# dcdc.net
KiCad netlist of a schematic drawn in EAGLE
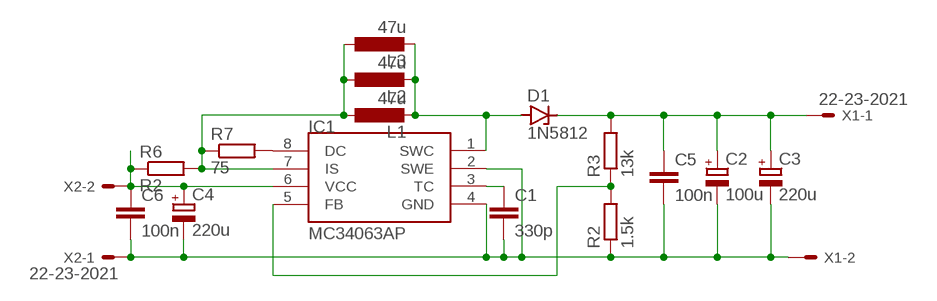
[diagram p0: schematic, sheet 1]

(export (version "E")
  (design (tool "Eeschema 10.0.6"))
  (components
    (comp (ref "C1")
      (value "330p")
      (footprint "eagle-import:C0805")
      (libsource (lib "eagle-import") (part "C-EUC0805"))
    )
    (comp (ref "C2")
      (value "100u")
      (footprint "eagle-import:E5-8,5")
      (libsource (lib "eagle-import") (part "CPOL-EUE5-8.5"))
    )
    (comp (ref "C3")
      (value "220u")
      (footprint "eagle-import:E5-8,5")
      (libsource (lib "eagle-import") (part "CPOL-EUE5-8.5"))
    )
    (comp (ref "C4")
      (value "220u")
      (footprint "eagle-import:E5-8,5")
      (libsource (lib "eagle-import") (part "CPOL-EUE5-8.5"))
    )
    (comp (ref "C5")
      (value "100n")
      (footprint "eagle-import:C0805")
      (libsource (lib "eagle-import") (part "C-EUC0805"))
    )
    (comp (ref "C6")
      (value "100n")
      (footprint "eagle-import:C0805")
      (libsource (lib "eagle-import") (part "C-EUC0805"))
    )
    (comp (ref "D1")
      (value "1N5812")
      (footprint "eagle-import:C1702-15")
      (libsource (lib "eagle-import") (part "1N5333"))
    )
    (comp (ref "IC1")
      (value "MC34063AP")
      (footprint "eagle-import:DIL08")
      (libsource (lib "eagle-import") (part "MC34063AP"))
    )
    (comp (ref "L1")
      (value "47u")
      (footprint "eagle-import:TJ3-U2")
      (libsource (lib "eagle-import") (part "L-EUTJ3-U2"))
    )
    (comp (ref "L2")
      (value "47u")
      (footprint "eagle-import:TJ4-U2")
      (libsource (lib "eagle-import") (part "L-EUTJ4-U2"))
    )
    (comp (ref "L3")
      (value "47u")
      (footprint "eagle-import:6000-XXXX-RC")
      (libsource (lib "eagle-import") (part "L-EU6000-XXX-RC"))
    )
    (comp (ref "R2")
      (value "1.5k")
      (footprint "eagle-import:R0805")
      (libsource (lib "eagle-import") (part "R-EU_R0805"))
    )
    (comp (ref "R3")
      (value "13k")
      (footprint "eagle-import:0204_7")
      (libsource (lib "eagle-import") (part "R-EU_0204/7"))
    )
    (comp (ref "R6")
      (value "R2")
      (footprint "eagle-import:R0805")
      (libsource (lib "eagle-import") (part "R-EU_R0805"))
    )
    (comp (ref "R7")
      (value "75")
      (footprint "eagle-import:R0805")
      (libsource (lib "eagle-import") (part "R-EU_R0805"))
    )
    (comp (ref "X1")
      (value "22-23-2021")
      (footprint "eagle-import:22-23-2021")
      (fields (field (name "MF") "MOLEX"))
      (libsource (lib "eagle-import") (part "22-23-2021"))
    )
    (comp (ref "X2")
      (value "22-23-2021")
      (footprint "eagle-import:22-23-2021")
      (fields (field (name "MF") "MOLEX"))
      (libsource (lib "eagle-import") (part "22-23-2021"))
    )
  )
  (nets
    (net (code "1") (name "Net-(IC1-DC)") (class "Default")
      (node (ref "IC1") (pin "8") (pinfunction "DC_8") (pintype "passive"))
      (node (ref "R7") (pin "2") (pinfunction "2_2") (pintype "passive"))
    )
    (net (code "2") (name "Net-(IC1-FB)") (class "Default")
      (node (ref "IC1") (pin "5") (pinfunction "FB_5") (pintype "passive"))
      (node (ref "R2") (pin "2") (pinfunction "2_2") (pintype "passive"))
      (node (ref "R3") (pin "1") (pinfunction "1_1") (pintype "passive"))
    )
    (net (code "3") (name "Net-(IC1-GND)") (class "Default")
      (node (ref "C1") (pin "2") (pinfunction "2_2") (pintype "passive"))
      (node (ref "C2") (pin "-") (pinfunction "-_-") (pintype "passive"))
      (node (ref "C3") (pin "-") (pinfunction "-_-") (pintype "passive"))
      (node (ref "C4") (pin "-") (pinfunction "-_-") (pintype "passive"))
      (node (ref "C5") (pin "2") (pinfunction "2_2") (pintype "passive"))
      (node (ref "C6") (pin "2") (pinfunction "2_2") (pintype "passive"))
      (node (ref "IC1") (pin "2") (pinfunction "SWE_2") (pintype "passive"))
      (node (ref "IC1") (pin "4") (pinfunction "GND_4") (pintype "passive"))
      (node (ref "R2") (pin "1") (pinfunction "1_1") (pintype "passive"))
      (node (ref "X1") (pin "2") (pinfunction "S_2") (pintype "passive"))
      (node (ref "X2") (pin "1") (pinfunction "S_1") (pintype "passive"))
    )
    (net (code "4") (name "Net-(IC1-IS)") (class "Default")
      (node (ref "IC1") (pin "7") (pinfunction "IS_7") (pintype "passive"))
      (node (ref "L1") (pin "1") (pinfunction "1_1") (pintype "passive"))
      (node (ref "L2") (pin "1") (pinfunction "1_1") (pintype "passive"))
      (node (ref "L3") (pin "1") (pinfunction "1_1") (pintype "passive"))
      (node (ref "R6") (pin "2") (pinfunction "2_2") (pintype "passive"))
      (node (ref "R7") (pin "1") (pinfunction "1_1") (pintype "passive"))
    )
    (net (code "5") (name "Net-(IC1-SWC)") (class "Default")
      (node (ref "D1") (pin "A") (pinfunction "A_A") (pintype "passive"))
      (node (ref "IC1") (pin "1") (pinfunction "SWC_1") (pintype "passive"))
      (node (ref "L1") (pin "2") (pinfunction "2_2") (pintype "passive"))
      (node (ref "L2") (pin "2") (pinfunction "2_2") (pintype "passive"))
      (node (ref "L3") (pin "2") (pinfunction "2_2") (pintype "passive"))
    )
    (net (code "6") (name "Net-(IC1-TC)") (class "Default")
      (node (ref "C1") (pin "1") (pinfunction "1_1") (pintype "passive"))
      (node (ref "IC1") (pin "3") (pinfunction "TC_3") (pintype "passive"))
    )
    (net (code "7") (name "Net-(IC1-VCC)") (class "Default")
      (node (ref "C4") (pin "+") (pinfunction "+_+") (pintype "passive"))
      (node (ref "C6") (pin "1") (pinfunction "1_1") (pintype "passive"))
      (node (ref "IC1") (pin "6") (pinfunction "VCC_6") (pintype "passive"))
      (node (ref "R6") (pin "1") (pinfunction "1_1") (pintype "passive"))
      (node (ref "X2") (pin "2") (pinfunction "S_2") (pintype "passive"))
    )
    (net (code "8") (name "Net-(X1A-S)") (class "Default")
      (node (ref "C2") (pin "+") (pinfunction "+_+") (pintype "passive"))
      (node (ref "C3") (pin "+") (pinfunction "+_+") (pintype "passive"))
      (node (ref "C5") (pin "1") (pinfunction "1_1") (pintype "passive"))
      (node (ref "D1") (pin "C") (pinfunction "C_C") (pintype "passive"))
      (node (ref "R3") (pin "2") (pinfunction "2_2") (pintype "passive"))
      (node (ref "X1") (pin "1") (pinfunction "S_1") (pintype "passive"))
    )
  )
)
